# analog_interface.net
KiCad netlist of a schematic drawn in Altium Designer
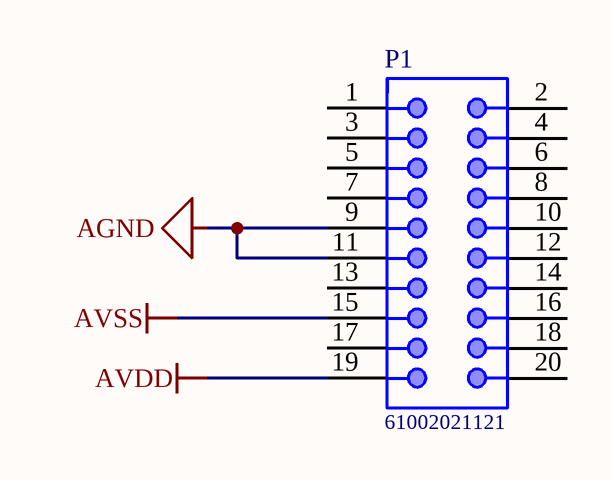
[diagram p0: analog_interface.SchDoc]

(export (version "E")
  (design (tool "Eeschema 10.0.6"))
  (components
    (comp (ref "P1")
      (value "61002021121")
      (footprint "61002021121")
      (description "SMT Vertical Pin Header WR-PHD, Pitch 2.54 mm, Dual Row, 20 pins")
      (fields (field (name "PUBLISHER") "Wurth Elektronik"))
      (libsource (lib "Pin Header WR-PHD_2.54 mm") (part "61002021121"))
    )
  )
  (nets
    (net (code "1") (name "AGND") (class "Default")
      (node (ref "P1") (pin "11") (pinfunction "11_11") (pintype "passive"))
      (node (ref "P1") (pin "9") (pinfunction "9_9") (pintype "passive"))
    )
    (net (code "2") (name "AVDD") (class "Default")
      (node (ref "P1") (pin "19") (pinfunction "19_19") (pintype "passive"))
    )
    (net (code "3") (name "AVSS") (class "Default")
      (node (ref "P1") (pin "15") (pinfunction "15_15") (pintype "passive"))
    )
    (net (code "4") (name "unconnected-(P1-Pad1)") (class "Default")
      (node (ref "P1") (pin "1") (pinfunction "1_1") (pintype "passive"))
    )
    (net (code "5") (name "unconnected-(P1-Pad2)") (class "Default")
      (node (ref "P1") (pin "2") (pinfunction "2_2") (pintype "passive"))
    )
    (net (code "6") (name "unconnected-(P1-Pad3)") (class "Default")
      (node (ref "P1") (pin "3") (pinfunction "3_3") (pintype "passive"))
    )
    (net (code "7") (name "unconnected-(P1-Pad4)") (class "Default")
      (node (ref "P1") (pin "4") (pinfunction "4_4") (pintype "passive"))
    )
    (net (code "8") (name "unconnected-(P1-Pad5)") (class "Default")
      (node (ref "P1") (pin "5") (pinfunction "5_5") (pintype "passive"))
    )
    (net (code "9") (name "unconnected-(P1-Pad6)") (class "Default")
      (node (ref "P1") (pin "6") (pinfunction "6_6") (pintype "passive"))
    )
    (net (code "10") (name "unconnected-(P1-Pad7)") (class "Default")
      (node (ref "P1") (pin "7") (pinfunction "7_7") (pintype "passive"))
    )
    (net (code "11") (name "unconnected-(P1-Pad8)") (class "Default")
      (node (ref "P1") (pin "8") (pinfunction "8_8") (pintype "passive"))
    )
    (net (code "12") (name "unconnected-(P1-Pad10)") (class "Default")
      (node (ref "P1") (pin "10") (pinfunction "10_10") (pintype "passive"))
    )
    (net (code "13") (name "unconnected-(P1-Pad12)") (class "Default")
      (node (ref "P1") (pin "12") (pinfunction "12_12") (pintype "passive"))
    )
    (net (code "14") (name "unconnected-(P1-Pad13)") (class "Default")
      (node (ref "P1") (pin "13") (pinfunction "13_13") (pintype "passive"))
    )
    (net (code "15") (name "unconnected-(P1-Pad14)") (class "Default")
      (node (ref "P1") (pin "14") (pinfunction "14_14") (pintype "passive"))
    )
    (net (code "16") (name "unconnected-(P1-Pad16)") (class "Default")
      (node (ref "P1") (pin "16") (pinfunction "16_16") (pintype "passive"))
    )
    (net (code "17") (name "unconnected-(P1-Pad17)") (class "Default")
      (node (ref "P1") (pin "17") (pinfunction "17_17") (pintype "passive"))
    )
    (net (code "18") (name "unconnected-(P1-Pad18)") (class "Default")
      (node (ref "P1") (pin "18") (pinfunction "18_18") (pintype "passive"))
    )
    (net (code "19") (name "unconnected-(P1-Pad20)") (class "Default")
      (node (ref "P1") (pin "20") (pinfunction "20_20") (pintype "passive"))
    )
  )
)
